# BAT_PROTECTOR.net
KiCad netlist of a schematic drawn in Altium Designer
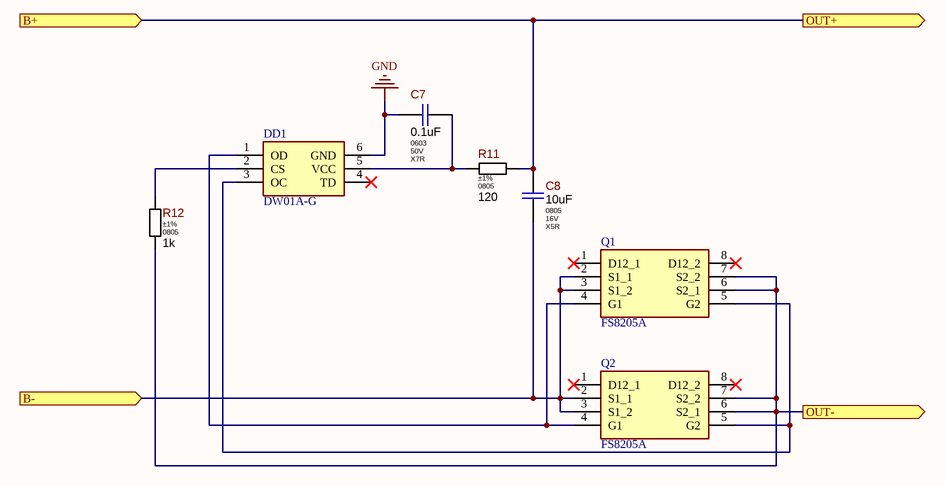
[diagram p0: BAT_PROTECTOR.SchDoc]

(export (version "E")
  (design (tool "Eeschema 10.0.6"))
  (components
    (comp (ref "C7")
      (value "0.1uF")
      (footprint "C_CERAMIC_0603_MED")
      (description "100nF 50V X7R ±10% 0603 Ceramic Capacitor RoHS")
      (fields
        (field (name "PACKAGE") "0603")
        (field (name "VOLTAGE") "50V")
        (field (name "DIELECTRIC TYPE") "X7R")
        (field (name "PART NUMBER") "CL10B104KB8NNND")
        (field (name "MANUFACTURER") "Samsung Electro-Mechanics")
      )
      (libsource (lib "capacitors") (part "CL10B104KB8NNND"))
    )
    (comp (ref "C8")
      (value "10uF")
      (footprint "CAP-0805(2012)X125T15")
      (description "10uF 16V Х5R ±10% 0805 Ceramic Capacitor RoHS")
      (fields
        (field (name "PACKAGE") "0805")
        (field (name "VOLTAGE") "16V")
        (field (name "DIELECTRIC TYPE") "X5R")
        (field (name "PART NUMBER") "CL21A106KOQNNNE")
        (field (name "MANUFACTURER") "Samsung Electro-Mechanics")
      )
      (libsource (lib "capacitors") (part "CL21A106KOQNNNE"))
    )
    (comp (ref "DD1")
      (value "DW01A-G")
      (footprint "DW01A-G")
      (description "One Cell Lithium-ion/Polymer Battery Protection IC")
      (libsource (lib "vitech_lib") (part "DW01A-G"))
    )
    (comp (ref "Q1")
      (value "FS8205A")
      (footprint "FS8205A")
      (description "Dual N-Channel Enahncement Mode Power MOSFET")
      (libsource (lib "vitech_lib") (part "FS8205A"))
    )
    (comp (ref "Q2")
      (value "FS8205A")
      (footprint "FS8205A")
      (description "Dual N-Channel Enahncement Mode Power MOSFET")
      (libsource (lib "vitech_lib") (part "FS8205A"))
    )
    (comp (ref "R11")
      (value "120")
      (footprint "R_ANY_CHIP_0805_MED")
      (description "120 Ohms ±1%, 1/8W 0805 Thick Film Resistor")
      (fields
        (field (name "TOLERANCE") "±1%")
        (field (name "PACKAGE") "0805")
        (field (name "PART NUMBER") "RC0805FR-07120RL")
        (field (name "MANUFACTURER") "Yageo")
      )
      (libsource (lib "resistors") (part "RC0805FR-07120RL"))
    )
    (comp (ref "R12")
      (value "1k")
      (footprint "R_ANY_CHIP_0805_MED")
      (description "1 kOhms ±1%, 1/8W 0805 Thick Film Resistor")
      (fields
        (field (name "TOLERANCE") "±1%")
        (field (name "PACKAGE") "0805")
        (field (name "PART NUMBER") "RC0805FR-071KL")
        (field (name "MANUFACTURER") "Yageo")
      )
      (libsource (lib "resistors") (part "RC0805FR-071KL"))
    )
  )
  (nets
    (net (code "1") (name "/B+") (class "Default")
      (node (ref "C8") (pin "1") (pinfunction "1_1") (pintype "passive"))
      (node (ref "R11") (pin "1") (pintype "passive"))
    )
    (net (code "2") (name "/B-") (class "Default")
      (node (ref "C8") (pin "2") (pinfunction "2_2") (pintype "passive"))
      (node (ref "Q1") (pin "2") (pinfunction "S1_1_2") (pintype "passive"))
      (node (ref "Q1") (pin "3") (pinfunction "S1_2_3") (pintype "passive"))
      (node (ref "Q2") (pin "2") (pinfunction "S1_1_2") (pintype "passive"))
      (node (ref "Q2") (pin "3") (pinfunction "S1_2_3") (pintype "passive"))
    )
    (net (code "3") (name "/OUT-") (class "Default")
      (node (ref "Q1") (pin "6") (pinfunction "S2_1_6") (pintype "passive"))
      (node (ref "Q1") (pin "7") (pinfunction "S2_2_7") (pintype "passive"))
      (node (ref "Q2") (pin "6") (pinfunction "S2_1_6") (pintype "passive"))
      (node (ref "Q2") (pin "7") (pinfunction "S2_2_7") (pintype "passive"))
      (node (ref "R12") (pin "1") (pintype "passive"))
    )
    (net (code "4") (name "GND") (class "Default")
      (node (ref "C7") (pin "1") (pinfunction "1_1") (pintype "passive"))
      (node (ref "DD1") (pin "6") (pinfunction "GND_6") (pintype "passive"))
    )
    (net (code "5") (name "Net-(DD1-CS)") (class "Default")
      (node (ref "DD1") (pin "2") (pinfunction "CS_2") (pintype "passive"))
      (node (ref "R12") (pin "2") (pintype "passive"))
    )
    (net (code "6") (name "Net-(DD1-OC)") (class "Default")
      (node (ref "DD1") (pin "3") (pinfunction "OC_3") (pintype "passive"))
      (node (ref "Q1") (pin "5") (pinfunction "G2_5") (pintype "passive"))
      (node (ref "Q2") (pin "5") (pinfunction "G2_5") (pintype "passive"))
    )
    (net (code "7") (name "Net-(DD1-OD)") (class "Default")
      (node (ref "DD1") (pin "1") (pinfunction "OD_1") (pintype "passive"))
      (node (ref "Q1") (pin "4") (pinfunction "G1_4") (pintype "passive"))
      (node (ref "Q2") (pin "4") (pinfunction "G1_4") (pintype "passive"))
    )
    (net (code "8") (name "Net-(DD1-VCC)") (class "Default")
      (node (ref "C7") (pin "2") (pinfunction "2_2") (pintype "passive"))
      (node (ref "DD1") (pin "5") (pinfunction "VCC_5") (pintype "passive"))
      (node (ref "R11") (pin "2") (pintype "passive"))
    )
    (net (code "9") (name "unconnected-(DD1-TD-Pad4)") (class "Default")
      (node (ref "DD1") (pin "4") (pinfunction "TD_4") (pintype "passive+no_connect"))
    )
    (net (code "10") (name "unconnected-(Q1-D12_1-Pad1)") (class "Default")
      (node (ref "Q1") (pin "1") (pinfunction "D12_1_1") (pintype "passive+no_connect"))
    )
    (net (code "11") (name "unconnected-(Q1-D12_2-Pad8)") (class "Default")
      (node (ref "Q1") (pin "8") (pinfunction "D12_2_8") (pintype "passive+no_connect"))
    )
    (net (code "12") (name "unconnected-(Q2-D12_1-Pad1)") (class "Default")
      (node (ref "Q2") (pin "1") (pinfunction "D12_1_1") (pintype "passive+no_connect"))
    )
    (net (code "13") (name "unconnected-(Q2-D12_2-Pad8)") (class "Default")
      (node (ref "Q2") (pin "8") (pinfunction "D12_2_8") (pintype "passive+no_connect"))
    )
  )
)
